# power.net
KiCad netlist of a schematic drawn in Altium Designer
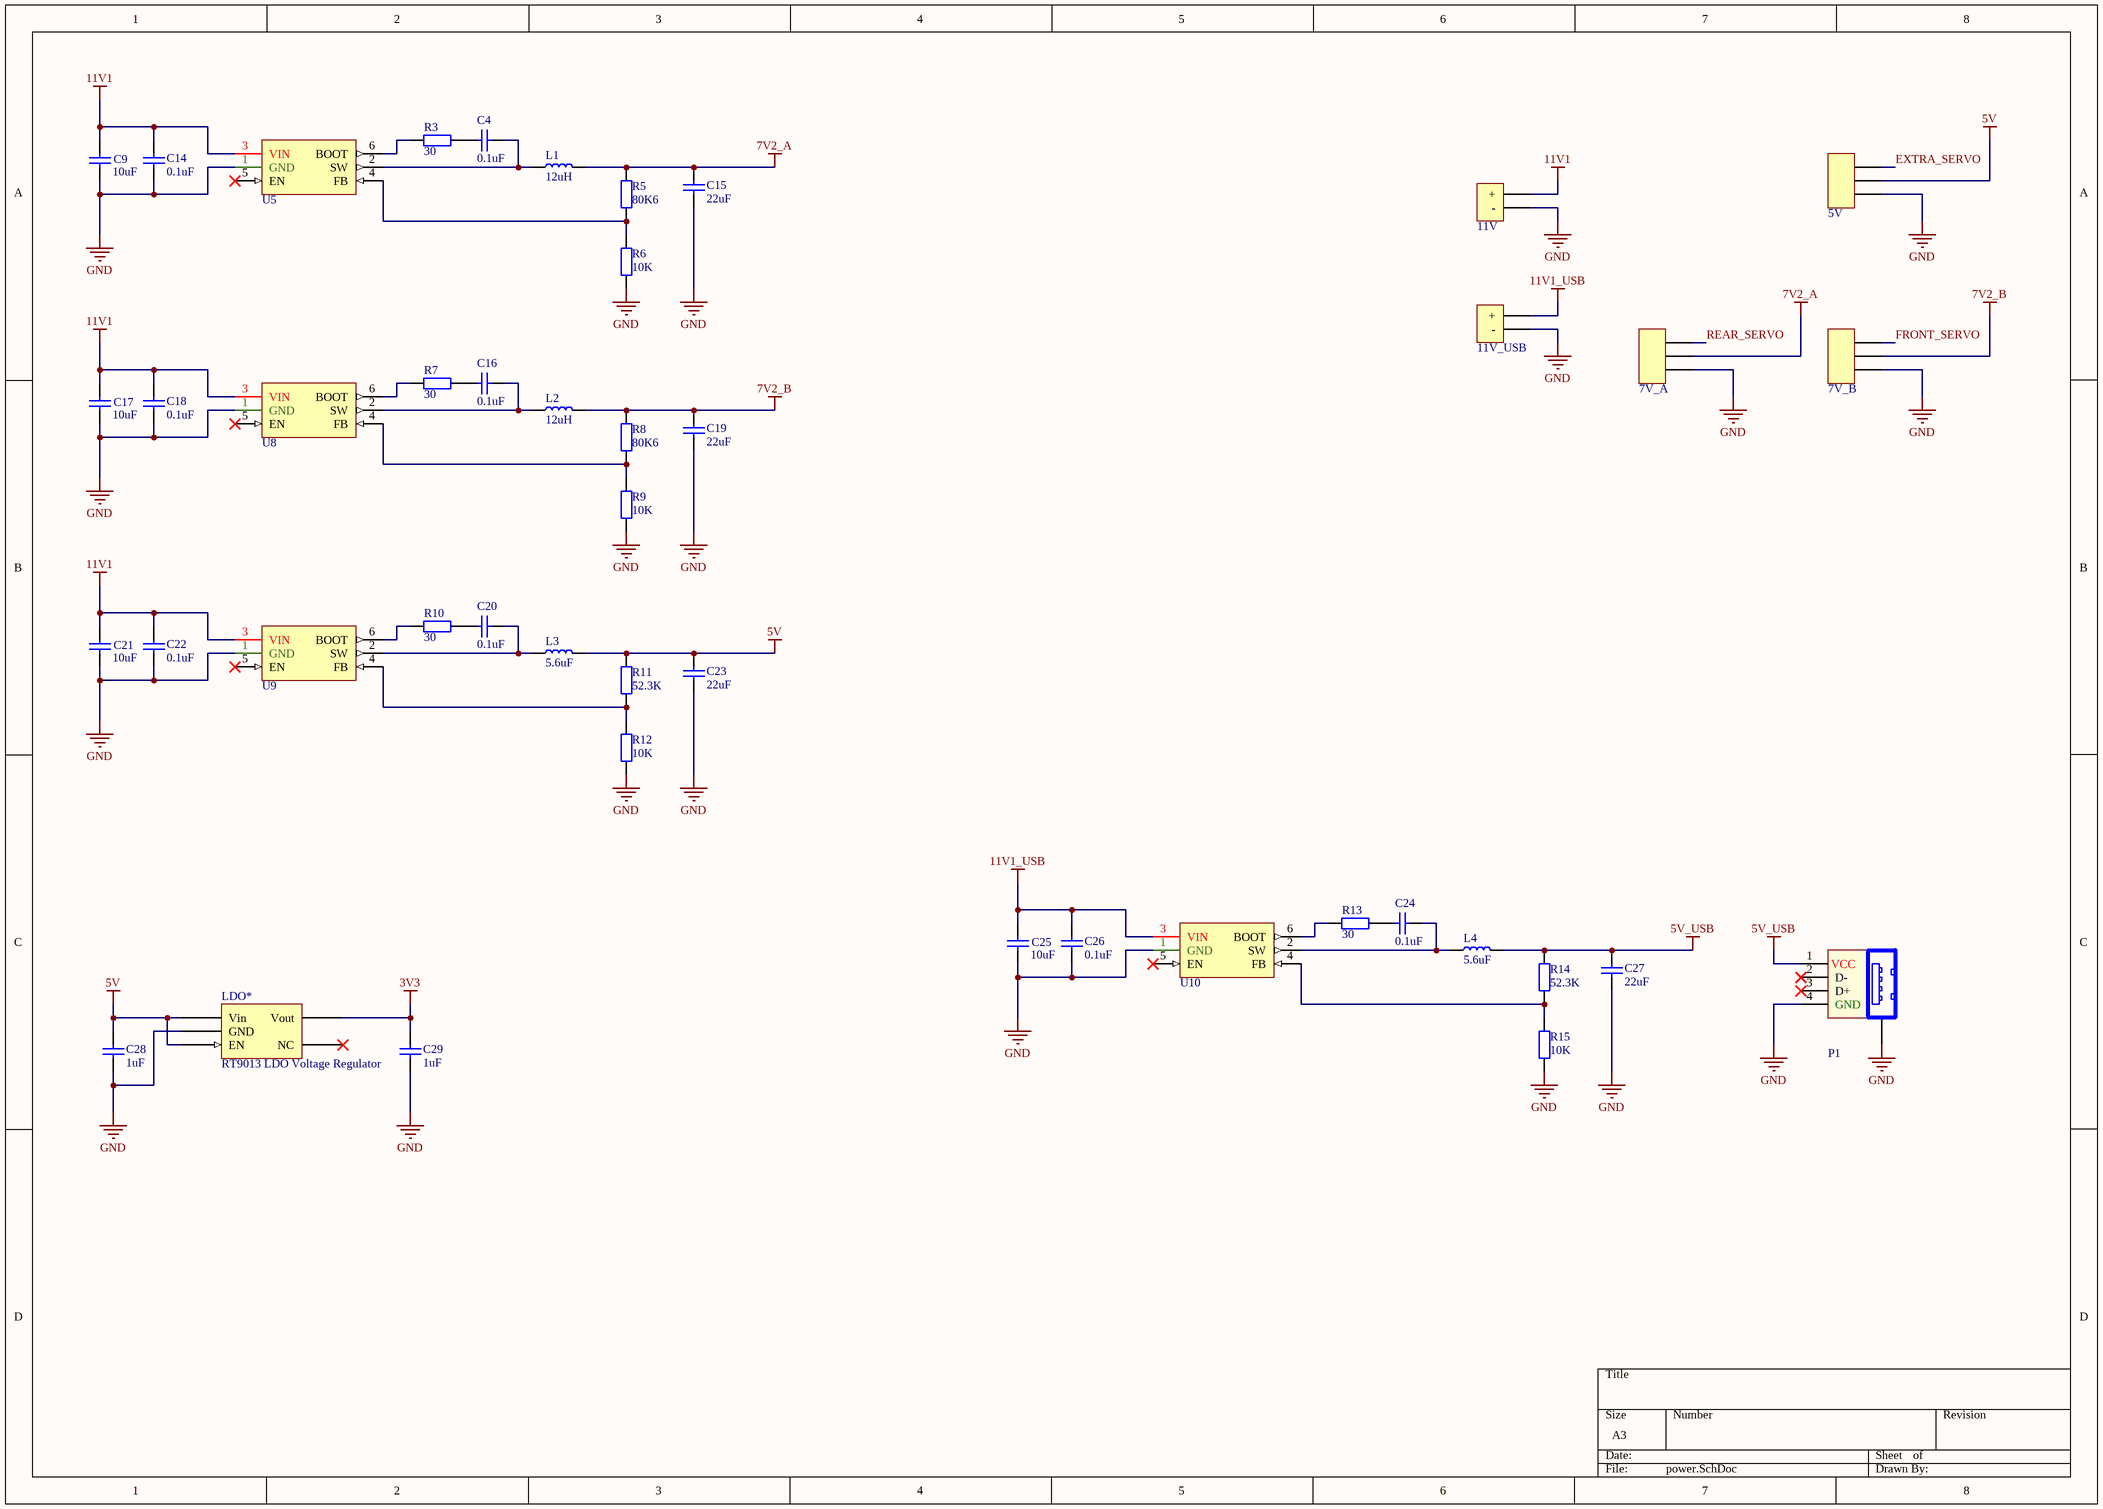
[diagram p0: power.SchDoc]

(export (version "E")
  (design (tool "Eeschema 10.0.6"))
  (components
    (comp (ref "5V")
      (value "3-Pin HEADER")
      (footprint "3-Pin HEADER")
      (libsource (lib "RobonAUT") (part "3-Pin HEADER"))
    )
    (comp (ref "7V_A")
      (value "3-Pin HEADER")
      (footprint "3-Pin HEADER")
      (libsource (lib "RobonAUT") (part "3-Pin HEADER"))
    )
    (comp (ref "7V_B")
      (value "3-Pin HEADER")
      (footprint "3-Pin HEADER")
      (libsource (lib "RobonAUT") (part "3-Pin HEADER"))
    )
    (comp (ref "11V")
      (value "T_PLUG")
      (footprint "T_plug")
      (description "LiPo battery T plug connector")
      (libsource (lib "HomeProjects") (part "T_PLUG"))
    )
    (comp (ref "11V_USB")
      (value "T_PLUG")
      (footprint "T_plug")
      (description "LiPo battery T plug connector")
      (libsource (lib "HomeProjects") (part "T_PLUG"))
    )
    (comp (ref "C4")
      (value "C0805C104M5RACTU")
      (footprint "0805")
      (description "Multilayer Ceramic Capacitors MLCC - SMD/SMT 50V 0.1uF X7R 0805 20%")
      (fields (field (name "CAPACITANCE") "0.1uF"))
      (libsource (lib "HomeProjects") (part "C0805C104M5RACTU"))
    )
    (comp (ref "C9")
      (value "GRM21BR61E106MA73L")
      (footprint "0805")
      (description "Multilayer Ceramic Capacitors MLCC - SMD/SMT 0805 10uF 25volts X5R 20%")
      (fields (field (name "CAPACITANCE") "10uF"))
      (libsource (lib "HomeProjects") (part "GRM21BR61E106MA73L"))
    )
    (comp (ref "C14")
      (value "C0805C104M5RACTU")
      (footprint "0805")
      (description "Multilayer Ceramic Capacitors MLCC - SMD/SMT 50V 0.1uF X7R 0805 20%")
      (fields (field (name "CAPACITANCE") "0.1uF"))
      (libsource (lib "HomeProjects") (part "C0805C104M5RACTU"))
    )
    (comp (ref "C15")
      (value "TMK325B7226KMHP")
      (footprint "1210")
      (description "Multilayer Ceramic Capacitors MLCC - SMD/SMT 1210 25V 22uF 10% X7R AEC-Q200")
      (fields (field (name "CAPACITANCE") "22uF"))
      (libsource (lib "HomeProjects") (part "TMK325B7226KMHP"))
    )
    (comp (ref "C16")
      (value "C0805C104M5RACTU")
      (footprint "0805")
      (description "Multilayer Ceramic Capacitors MLCC - SMD/SMT 50V 0.1uF X7R 0805 20%")
      (fields (field (name "CAPACITANCE") "0.1uF"))
      (libsource (lib "HomeProjects") (part "C0805C104M5RACTU"))
    )
    (comp (ref "C17")
      (value "GRM21BR61E106MA73L")
      (footprint "0805")
      (description "Multilayer Ceramic Capacitors MLCC - SMD/SMT 0805 10uF 25volts X5R 20%")
      (fields (field (name "CAPACITANCE") "10uF"))
      (libsource (lib "HomeProjects") (part "GRM21BR61E106MA73L"))
    )
    (comp (ref "C18")
      (value "C0805C104M5RACTU")
      (footprint "0805")
      (description "Multilayer Ceramic Capacitors MLCC - SMD/SMT 50V 0.1uF X7R 0805 20%")
      (fields (field (name "CAPACITANCE") "0.1uF"))
      (libsource (lib "HomeProjects") (part "C0805C104M5RACTU"))
    )
    (comp (ref "C19")
      (value "TMK325B7226KMHP")
      (footprint "1210")
      (description "Multilayer Ceramic Capacitors MLCC - SMD/SMT 1210 25V 22uF 10% X7R AEC-Q200")
      (fields (field (name "CAPACITANCE") "22uF"))
      (libsource (lib "HomeProjects") (part "TMK325B7226KMHP"))
    )
    (comp (ref "C20")
      (value "C0805C104M5RACTU")
      (footprint "0805")
      (description "Multilayer Ceramic Capacitors MLCC - SMD/SMT 50V 0.1uF X7R 0805 20%")
      (fields (field (name "CAPACITANCE") "0.1uF"))
      (libsource (lib "HomeProjects") (part "C0805C104M5RACTU"))
    )
    (comp (ref "C21")
      (value "GRM21BR61E106MA73L")
      (footprint "0805")
      (description "Multilayer Ceramic Capacitors MLCC - SMD/SMT 0805 10uF 25volts X5R 20%")
      (fields (field (name "CAPACITANCE") "10uF"))
      (libsource (lib "HomeProjects") (part "GRM21BR61E106MA73L"))
    )
    (comp (ref "C22")
      (value "C0805C104M5RACTU")
      (footprint "0805")
      (description "Multilayer Ceramic Capacitors MLCC - SMD/SMT 50V 0.1uF X7R 0805 20%")
      (fields (field (name "CAPACITANCE") "0.1uF"))
      (libsource (lib "HomeProjects") (part "C0805C104M5RACTU"))
    )
    (comp (ref "C23")
      (value "TMK325B7226KMHP")
      (footprint "1210")
      (description "Multilayer Ceramic Capacitors MLCC - SMD/SMT 1210 25V 22uF 10% X7R AEC-Q200")
      (fields (field (name "CAPACITANCE") "22uF"))
      (libsource (lib "HomeProjects") (part "TMK325B7226KMHP"))
    )
    (comp (ref "C24")
      (value "C0805C104M5RACTU")
      (footprint "0805")
      (description "Multilayer Ceramic Capacitors MLCC - SMD/SMT 50V 0.1uF X7R 0805 20%")
      (fields (field (name "CAPACITANCE") "0.1uF"))
      (libsource (lib "HomeProjects") (part "C0805C104M5RACTU"))
    )
    (comp (ref "C25")
      (value "GRM21BR61E106MA73L")
      (footprint "0805")
      (description "Multilayer Ceramic Capacitors MLCC - SMD/SMT 0805 10uF 25volts X5R 20%")
      (fields (field (name "CAPACITANCE") "10uF"))
      (libsource (lib "HomeProjects") (part "GRM21BR61E106MA73L"))
    )
    (comp (ref "C26")
      (value "C0805C104M5RACTU")
      (footprint "0805")
      (description "Multilayer Ceramic Capacitors MLCC - SMD/SMT 50V 0.1uF X7R 0805 20%")
      (fields (field (name "CAPACITANCE") "0.1uF"))
      (libsource (lib "HomeProjects") (part "C0805C104M5RACTU"))
    )
    (comp (ref "C27")
      (value "TMK325B7226KMHP")
      (footprint "1210")
      (description "Multilayer Ceramic Capacitors MLCC - SMD/SMT 1210 25V 22uF 10% X7R AEC-Q200")
      (fields (field (name "CAPACITANCE") "22uF"))
      (libsource (lib "HomeProjects") (part "TMK325B7226KMHP"))
    )
    (comp (ref "C28")
      (value "VJ0805Y105KXQTW1BC")
      (footprint "0805")
      (description "SMD Multilayer Ceramic Capacitor, 0805 [2012 Metric], 1 µF, 10 V, ± 10%, X7R, VJ Series")
      (fields (field (name "CAPACITANCE") "1uF"))
      (libsource (lib "RobonAUT") (part "VJ0805Y105KXQTW1BC"))
    )
    (comp (ref "C29")
      (value "VJ0805Y105KXQTW1BC")
      (footprint "0805")
      (description "SMD Multilayer Ceramic Capacitor, 0805 [2012 Metric], 1 µF, 10 V, ± 10%, X7R, VJ Series")
      (fields (field (name "CAPACITANCE") "1uF"))
      (libsource (lib "RobonAUT") (part "VJ0805Y105KXQTW1BC"))
    )
    (comp (ref "L1")
      (value "SDR1307-120ML")
      (footprint "SDR1307")
      (description "Fixed Inductors 12uH 20% SMD 1307")
      (fields (field (name "INDUCTANCE") "12uH"))
      (libsource (lib "HomeProjects") (part "SDR1307-120ML"))
    )
    (comp (ref "L2")
      (value "SDR1307-120ML")
      (footprint "SDR1307")
      (description "Fixed Inductors 12uH 20% SMD 1307")
      (fields (field (name "INDUCTANCE") "12uH"))
      (libsource (lib "HomeProjects") (part "SDR1307-120ML"))
    )
    (comp (ref "L3")
      (value "SDR1307-5R6ML")
      (footprint "SDR1307")
      (description "Fixed Inductors 5.6uH 20% SMD 1307")
      (fields (field (name "INDUCTANCE") "5.6uF"))
      (libsource (lib "HomeProjects") (part "SDR1307-5R6ML"))
    )
    (comp (ref "L4")
      (value "SDR1307-5R6ML")
      (footprint "SDR1307")
      (description "Fixed Inductors 5.6uH 20% SMD 1307")
      (fields (field (name "INDUCTANCE") "5.6uF"))
      (libsource (lib "HomeProjects") (part "SDR1307-5R6ML"))
    )
    (comp (ref "LDO*")
      (value "RT9013 LDO Voltage Regulator")
      (footprint "RT9013_SOT23")
      (description "LDO Voltage Regulator")
      (libsource (lib "mylib") (part "RT9013"))
    )
    (comp (ref "P1")
      (value "MC32593")
      (footprint "MC32593")
      (description "USB Connector, USB Type A, USB 2.0, Receptacle, 4 Ways, Through Hole Mount, Right Angle")
      (libsource (lib "HomeProjects") (part "MC32593"))
    )
    (comp (ref "R3")
      (value "RC0603FR-0730RL")
      (footprint "0603_RES")
      (description "Thick Film Resistors - SMD 30 OHM 1%")
      (fields (field (name "RESISTANCE") "30"))
      (libsource (lib "HomeProjects") (part "RC0603FR-0730RL"))
    )
    (comp (ref "R5")
      (value "CRCW060380K6FKEA")
      (footprint "0603_RES")
      (description "Thick Film Resistors - SMD 1/10watt 80.6Kohms 1%")
      (fields (field (name "RESISTANCE") "80K6"))
      (libsource (lib "HomeProjects") (part "CRCW060380K6FKEA"))
    )
    (comp (ref "R6")
      (value "CRCW060310K0FKEA")
      (footprint "0603_RES")
      (description "Thick Film Resistors - SMD 1/10watt 10Kohms 1%")
      (fields (field (name "RESISTANCE") "10K"))
      (libsource (lib "HomeProjects") (part "CRCW060310K0FKEA"))
    )
    (comp (ref "R7")
      (value "RC0603FR-0730RL")
      (footprint "0603_RES")
      (description "Thick Film Resistors - SMD 30 OHM 1%")
      (fields (field (name "RESISTANCE") "30"))
      (libsource (lib "HomeProjects") (part "RC0603FR-0730RL"))
    )
    (comp (ref "R8")
      (value "CRCW060380K6FKEA")
      (footprint "0603_RES")
      (description "Thick Film Resistors - SMD 1/10watt 80.6Kohms 1%")
      (fields (field (name "RESISTANCE") "80K6"))
      (libsource (lib "HomeProjects") (part "CRCW060380K6FKEA"))
    )
    (comp (ref "R9")
      (value "CRCW060310K0FKEA")
      (footprint "0603_RES")
      (description "Thick Film Resistors - SMD 1/10watt 10Kohms 1%")
      (fields (field (name "RESISTANCE") "10K"))
      (libsource (lib "HomeProjects") (part "CRCW060310K0FKEA"))
    )
    (comp (ref "R10")
      (value "RC0603FR-0730RL")
      (footprint "0603_RES")
      (description "Thick Film Resistors - SMD 30 OHM 1%")
      (fields (field (name "RESISTANCE") "30"))
      (libsource (lib "HomeProjects") (part "RC0603FR-0730RL"))
    )
    (comp (ref "R11")
      (value "CRCW060352K3FKEA")
      (footprint "0603_RES")
      (description "Thick Film Resistors - SMD 1/10watt 52.3Kohms 1%")
      (fields (field (name "RESISTANCE") "52.3K"))
      (libsource (lib "HomeProjects") (part "CRCW060352K3FKEA"))
    )
    (comp (ref "R12")
      (value "CRCW060310K0FKEA")
      (footprint "0603_RES")
      (description "Thick Film Resistors - SMD 1/10watt 10Kohms 1%")
      (fields (field (name "RESISTANCE") "10K"))
      (libsource (lib "HomeProjects") (part "CRCW060310K0FKEA"))
    )
    (comp (ref "R13")
      (value "RC0603FR-0730RL")
      (footprint "0603_RES")
      (description "Thick Film Resistors - SMD 30 OHM 1%")
      (fields (field (name "RESISTANCE") "30"))
      (libsource (lib "HomeProjects") (part "RC0603FR-0730RL"))
    )
    (comp (ref "R14")
      (value "CRCW060352K3FKEA")
      (footprint "0603_RES")
      (description "Thick Film Resistors - SMD 1/10watt 52.3Kohms 1%")
      (fields (field (name "RESISTANCE") "52.3K"))
      (libsource (lib "HomeProjects") (part "CRCW060352K3FKEA"))
    )
    (comp (ref "R15")
      (value "CRCW060310K0FKEA")
      (footprint "0603_RES")
      (description "Thick Film Resistors - SMD 1/10watt 10Kohms 1%")
      (fields (field (name "RESISTANCE") "10K"))
      (libsource (lib "HomeProjects") (part "CRCW060310K0FKEA"))
    )
    (comp (ref "U5")
      (value "TPS56339")
      (footprint "SOT-23-Thin-6")
      (description "4.5-V to 24-V Input, 3-A Output Synchronous Buck Converter")
      (libsource (lib "HomeProjects") (part "TPS56339"))
    )
    (comp (ref "U8")
      (value "TPS56339")
      (footprint "SOT-23-Thin-6")
      (description "4.5-V to 24-V Input, 3-A Output Synchronous Buck Converter")
      (libsource (lib "HomeProjects") (part "TPS56339"))
    )
    (comp (ref "U9")
      (value "TPS56339")
      (footprint "SOT-23-Thin-6")
      (description "4.5-V to 24-V Input, 3-A Output Synchronous Buck Converter")
      (libsource (lib "HomeProjects") (part "TPS56339"))
    )
    (comp (ref "U10")
      (value "TPS56339")
      (footprint "SOT-23-Thin-6")
      (description "4.5-V to 24-V Input, 3-A Output Synchronous Buck Converter")
      (libsource (lib "HomeProjects") (part "TPS56339"))
    )
  )
  (nets
    (net (code "1") (name "/EXTRA_SERVO") (class "Default")
      (node (ref "5V") (pin "1") (pinfunction "1_1") (pintype "passive"))
    )
    (net (code "2") (name "/FRONT_SERVO") (class "Default")
      (node (ref "7V_B") (pin "1") (pinfunction "1_1") (pintype "passive"))
    )
    (net (code "3") (name "/REAR_SERVO") (class "Default")
      (node (ref "7V_A") (pin "1") (pinfunction "1_1") (pintype "passive"))
    )
    (net (code "4") (name "3V3") (class "Default")
      (node (ref "C29") (pin "2") (pinfunction "2_2") (pintype "passive"))
      (node (ref "LDO*") (pin "Vout") (pinfunction "Vout_Vout") (pintype "power_in"))
    )
    (net (code "5") (name "5V") (class "Default")
      (node (ref "5V") (pin "2") (pinfunction "2_2") (pintype "passive"))
      (node (ref "C23") (pin "2") (pinfunction "2_2") (pintype "passive"))
      (node (ref "C28") (pin "2") (pinfunction "2_2") (pintype "passive"))
      (node (ref "L3") (pin "2") (pinfunction "2_2") (pintype "passive"))
      (node (ref "LDO*") (pin "EN") (pinfunction "EN_EN") (pintype "input"))
      (node (ref "LDO*") (pin "Vin") (pinfunction "Vin_Vin") (pintype "power_in"))
      (node (ref "R11") (pin "2") (pinfunction "2_2") (pintype "passive"))
    )
    (net (code "6") (name "5V_USB") (class "Default")
      (node (ref "C27") (pin "2") (pinfunction "2_2") (pintype "passive"))
      (node (ref "L4") (pin "2") (pinfunction "2_2") (pintype "passive"))
      (node (ref "P1") (pin "1") (pinfunction "VCC_1") (pintype "passive"))
      (node (ref "R14") (pin "2") (pinfunction "2_2") (pintype "passive"))
    )
    (net (code "7") (name "7V2_A") (class "Default")
      (node (ref "7V_A") (pin "2") (pinfunction "2_2") (pintype "passive"))
      (node (ref "C15") (pin "2") (pinfunction "2_2") (pintype "passive"))
      (node (ref "L1") (pin "2") (pinfunction "2_2") (pintype "passive"))
      (node (ref "R5") (pin "2") (pinfunction "2_2") (pintype "passive"))
    )
    (net (code "8") (name "7V2_B") (class "Default")
      (node (ref "7V_B") (pin "2") (pinfunction "2_2") (pintype "passive"))
      (node (ref "C19") (pin "2") (pinfunction "2_2") (pintype "passive"))
      (node (ref "L2") (pin "2") (pinfunction "2_2") (pintype "passive"))
      (node (ref "R8") (pin "2") (pinfunction "2_2") (pintype "passive"))
    )
    (net (code "9") (name "11V1") (class "Default")
      (node (ref "11V") (pin "1") (pinfunction "+_1") (pintype "passive"))
      (node (ref "C14") (pin "2") (pinfunction "2_2") (pintype "passive"))
      (node (ref "C17") (pin "2") (pinfunction "2_2") (pintype "passive"))
      (node (ref "C18") (pin "2") (pinfunction "2_2") (pintype "passive"))
      (node (ref "C21") (pin "2") (pinfunction "2_2") (pintype "passive"))
      (node (ref "C22") (pin "2") (pinfunction "2_2") (pintype "passive"))
      (node (ref "C9") (pin "2") (pinfunction "2_2") (pintype "passive"))
      (node (ref "U5") (pin "3") (pinfunction "VIN_3") (pintype "power_in"))
      (node (ref "U8") (pin "3") (pinfunction "VIN_3") (pintype "power_in"))
      (node (ref "U9") (pin "3") (pinfunction "VIN_3") (pintype "power_in"))
    )
    (net (code "10") (name "11V1_USB") (class "Default")
      (node (ref "11V_USB") (pin "1") (pinfunction "+_1") (pintype "passive"))
      (node (ref "C25") (pin "2") (pinfunction "2_2") (pintype "passive"))
      (node (ref "C26") (pin "2") (pinfunction "2_2") (pintype "passive"))
      (node (ref "U10") (pin "3") (pinfunction "VIN_3") (pintype "power_in"))
    )
    (net (code "11") (name "GND") (class "Default")
      (node (ref "11V") (pin "2") (pinfunction "-_2") (pintype "passive"))
      (node (ref "11V_USB") (pin "2") (pinfunction "-_2") (pintype "passive"))
      (node (ref "5V") (pin "3") (pinfunction "3_3") (pintype "passive"))
      (node (ref "7V_A") (pin "3") (pinfunction "3_3") (pintype "passive"))
      (node (ref "7V_B") (pin "3") (pinfunction "3_3") (pintype "passive"))
      (node (ref "C14") (pin "1") (pinfunction "1_1") (pintype "passive"))
      (node (ref "C15") (pin "1") (pinfunction "1_1") (pintype "passive"))
      (node (ref "C17") (pin "1") (pinfunction "1_1") (pintype "passive"))
      (node (ref "C18") (pin "1") (pinfunction "1_1") (pintype "passive"))
      (node (ref "C19") (pin "1") (pinfunction "1_1") (pintype "passive"))
      (node (ref "C21") (pin "1") (pinfunction "1_1") (pintype "passive"))
      (node (ref "C22") (pin "1") (pinfunction "1_1") (pintype "passive"))
      (node (ref "C23") (pin "1") (pinfunction "1_1") (pintype "passive"))
      (node (ref "C25") (pin "1") (pinfunction "1_1") (pintype "passive"))
      (node (ref "C26") (pin "1") (pinfunction "1_1") (pintype "passive"))
      (node (ref "C27") (pin "1") (pinfunction "1_1") (pintype "passive"))
      (node (ref "C28") (pin "1") (pinfunction "1_1") (pintype "passive"))
      (node (ref "C29") (pin "1") (pinfunction "1_1") (pintype "passive"))
      (node (ref "C9") (pin "1") (pinfunction "1_1") (pintype "passive"))
      (node (ref "LDO*") (pin "GND") (pinfunction "GND_GND") (pintype "power_in"))
      (node (ref "P1") (pin "0") (pinfunction "MNT/GND_0") (pintype "passive"))
      (node (ref "P1") (pin "4") (pinfunction "GND_4") (pintype "power_in"))
      (node (ref "R12") (pin "1") (pinfunction "1_1") (pintype "passive"))
      (node (ref "R15") (pin "1") (pinfunction "1_1") (pintype "passive"))
      (node (ref "R6") (pin "1") (pinfunction "1_1") (pintype "passive"))
      (node (ref "R9") (pin "1") (pinfunction "1_1") (pintype "passive"))
      (node (ref "U10") (pin "1") (pinfunction "GND_1") (pintype "power_in"))
      (node (ref "U5") (pin "1") (pinfunction "GND_1") (pintype "power_in"))
      (node (ref "U8") (pin "1") (pinfunction "GND_1") (pintype "power_in"))
      (node (ref "U9") (pin "1") (pinfunction "GND_1") (pintype "power_in"))
    )
    (net (code "12") (name "Net-(C4-Pad1)") (class "Default")
      (node (ref "C4") (pin "1") (pinfunction "1_1") (pintype "passive"))
      (node (ref "R3") (pin "2") (pinfunction "2_2") (pintype "passive"))
    )
    (net (code "13") (name "Net-(C16-Pad1)") (class "Default")
      (node (ref "C16") (pin "1") (pinfunction "1_1") (pintype "passive"))
      (node (ref "R7") (pin "2") (pinfunction "2_2") (pintype "passive"))
    )
    (net (code "14") (name "Net-(C20-Pad1)") (class "Default")
      (node (ref "C20") (pin "1") (pinfunction "1_1") (pintype "passive"))
      (node (ref "R10") (pin "2") (pinfunction "2_2") (pintype "passive"))
    )
    (net (code "15") (name "Net-(C24-Pad1)") (class "Default")
      (node (ref "C24") (pin "1") (pinfunction "1_1") (pintype "passive"))
      (node (ref "R13") (pin "2") (pinfunction "2_2") (pintype "passive"))
    )
    (net (code "16") (name "Net-(U5-BOOT)") (class "Default")
      (node (ref "R3") (pin "1") (pinfunction "1_1") (pintype "passive"))
      (node (ref "U5") (pin "6") (pinfunction "BOOT_6") (pintype "output"))
    )
    (net (code "17") (name "Net-(U5-FB)") (class "Default")
      (node (ref "R5") (pin "1") (pinfunction "1_1") (pintype "passive"))
      (node (ref "R6") (pin "2") (pinfunction "2_2") (pintype "passive"))
      (node (ref "U5") (pin "4") (pinfunction "FB_4") (pintype "input"))
    )
    (net (code "18") (name "Net-(U5-SW)") (class "Default")
      (node (ref "C4") (pin "2") (pinfunction "2_2") (pintype "passive"))
      (node (ref "L1") (pin "1") (pinfunction "1_1") (pintype "passive"))
      (node (ref "U5") (pin "2") (pinfunction "SW_2") (pintype "output"))
    )
    (net (code "19") (name "Net-(U8-BOOT)") (class "Default")
      (node (ref "R7") (pin "1") (pinfunction "1_1") (pintype "passive"))
      (node (ref "U8") (pin "6") (pinfunction "BOOT_6") (pintype "output"))
    )
    (net (code "20") (name "Net-(U8-FB)") (class "Default")
      (node (ref "R8") (pin "1") (pinfunction "1_1") (pintype "passive"))
      (node (ref "R9") (pin "2") (pinfunction "2_2") (pintype "passive"))
      (node (ref "U8") (pin "4") (pinfunction "FB_4") (pintype "input"))
    )
    (net (code "21") (name "Net-(U8-SW)") (class "Default")
      (node (ref "C16") (pin "2") (pinfunction "2_2") (pintype "passive"))
      (node (ref "L2") (pin "1") (pinfunction "1_1") (pintype "passive"))
      (node (ref "U8") (pin "2") (pinfunction "SW_2") (pintype "output"))
    )
    (net (code "22") (name "Net-(U9-BOOT)") (class "Default")
      (node (ref "R10") (pin "1") (pinfunction "1_1") (pintype "passive"))
      (node (ref "U9") (pin "6") (pinfunction "BOOT_6") (pintype "output"))
    )
    (net (code "23") (name "Net-(U9-FB)") (class "Default")
      (node (ref "R11") (pin "1") (pinfunction "1_1") (pintype "passive"))
      (node (ref "R12") (pin "2") (pinfunction "2_2") (pintype "passive"))
      (node (ref "U9") (pin "4") (pinfunction "FB_4") (pintype "input"))
    )
    (net (code "24") (name "Net-(U9-SW)") (class "Default")
      (node (ref "C20") (pin "2") (pinfunction "2_2") (pintype "passive"))
      (node (ref "L3") (pin "1") (pinfunction "1_1") (pintype "passive"))
      (node (ref "U9") (pin "2") (pinfunction "SW_2") (pintype "output"))
    )
    (net (code "25") (name "Net-(U10-BOOT)") (class "Default")
      (node (ref "R13") (pin "1") (pinfunction "1_1") (pintype "passive"))
      (node (ref "U10") (pin "6") (pinfunction "BOOT_6") (pintype "output"))
    )
    (net (code "26") (name "Net-(U10-FB)") (class "Default")
      (node (ref "R14") (pin "1") (pinfunction "1_1") (pintype "passive"))
      (node (ref "R15") (pin "2") (pinfunction "2_2") (pintype "passive"))
      (node (ref "U10") (pin "4") (pinfunction "FB_4") (pintype "input"))
    )
    (net (code "27") (name "Net-(U10-SW)") (class "Default")
      (node (ref "C24") (pin "2") (pinfunction "2_2") (pintype "passive"))
      (node (ref "L4") (pin "1") (pinfunction "1_1") (pintype "passive"))
      (node (ref "U10") (pin "2") (pinfunction "SW_2") (pintype "output"))
    )
    (net (code "28") (name "unconnected-(LDO*-PadNC)") (class "Default")
      (node (ref "LDO*") (pin "NC") (pinfunction "NC_NC") (pintype "passive+no_connect"))
    )
    (net (code "29") (name "unconnected-(P1-D+-Pad3)") (class "Default")
      (node (ref "P1") (pin "3") (pinfunction "D+_3") (pintype "passive+no_connect"))
    )
    (net (code "30") (name "unconnected-(P1-D--Pad2)") (class "Default")
      (node (ref "P1") (pin "2") (pinfunction "D-_2") (pintype "passive+no_connect"))
    )
    (net (code "31") (name "unconnected-(U5-EN-Pad5)") (class "Default")
      (node (ref "U5") (pin "5") (pinfunction "EN_5") (pintype "input+no_connect"))
    )
    (net (code "32") (name "unconnected-(U8-EN-Pad5)") (class "Default")
      (node (ref "U8") (pin "5") (pinfunction "EN_5") (pintype "input+no_connect"))
    )
    (net (code "33") (name "unconnected-(U9-EN-Pad5)") (class "Default")
      (node (ref "U9") (pin "5") (pinfunction "EN_5") (pintype "input+no_connect"))
    )
    (net (code "34") (name "unconnected-(U10-EN-Pad5)") (class "Default")
      (node (ref "U10") (pin "5") (pinfunction "EN_5") (pintype "input+no_connect"))
    )
  )
)
